# RF_Ticketing_Slave.net
KiCad netlist of a schematic drawn in Altium Designer
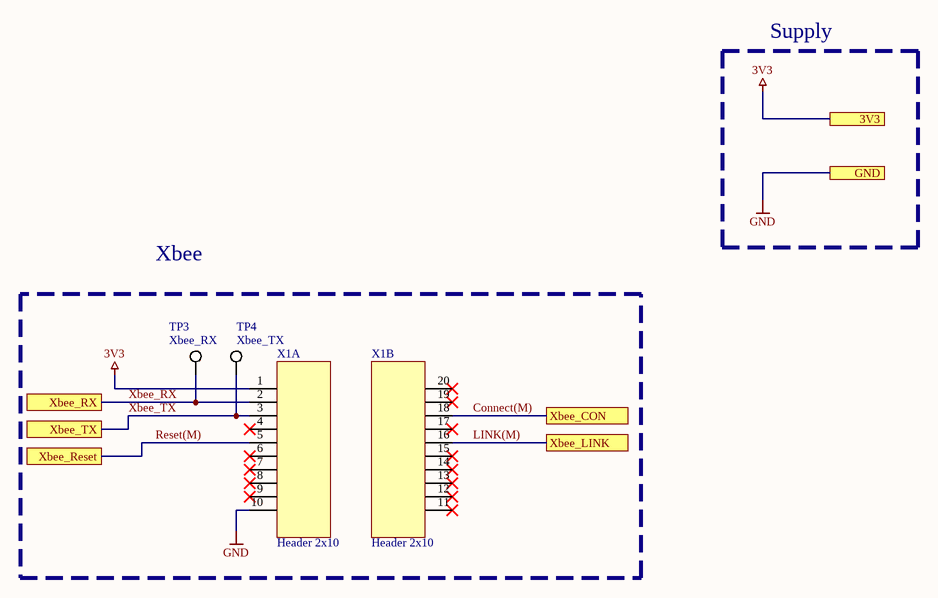
[diagram p0: RF_Ticketing_Slave.SchDoc]

(export (version "E")
  (design (tool "Eeschema 10.0.6"))
  (components
    (comp (ref "TP3")
      (value "Xbee_RX")
      (footprint "KSTN-5019_V")
      (description "Test Point, 1 Position SMD, RoHS, Tape and Reel")
      (libsource (lib "Altium Content Vault") (part "TESTPOINT_WHITE"))
    )
    (comp (ref "TP4")
      (value "Xbee_TX")
      (footprint "KSTN-5019_V")
      (description "Test Point, 1 Position SMD, RoHS, Tape and Reel")
      (libsource (lib "Altium Content Vault") (part "TESTPOINT_WHITE"))
    )
    (comp (ref "X1")
      (value "Header 2x10")
      (footprint "ZB-SB")
      (description "Header 2x10\r\nXbee de letml(1623) ou xbee XB24CAUIT-001")
      (libsource (lib "PCB_Ticketing_Slave") (part "HDR ZB-SB 2x10_1"))
    )
  )
  (nets
    (net (code "1") (name "/Connect(M)") (class "Default") (node (ref "X1") (pin "18") (pintype "passive")))
    (net (code "2") (name "/LINK(M)") (class "Default") (node (ref "X1") (pin "16") (pintype "passive")))
    (net (code "3") (name "/Reset(M)") (class "Default") (node (ref "X1") (pin "5") (pintype "passive")))
    (net (code "4") (name "/Xbee_RX") (class "Default")
      (node (ref "TP3") (pin "1") (pinfunction "1_1") (pintype "passive"))
      (node (ref "X1") (pin "2") (pintype "passive"))
    )
    (net (code "5") (name "/Xbee_TX") (class "Default")
      (node (ref "TP4") (pin "1") (pinfunction "1_1") (pintype "passive"))
      (node (ref "X1") (pin "3") (pintype "passive"))
    )
    (net (code "6") (name "3V3") (class "Default") (node (ref "X1") (pin "1") (pintype "passive")))
    (net (code "7") (name "GND") (class "Default") (node (ref "X1") (pin "10") (pintype "passive")))
    (net (code "8") (name "unconnected-(X1-Pad4)") (class "Default")
      (node (ref "X1") (pin "4") (pintype "passive+no_connect"))
    )
    (net (code "9") (name "unconnected-(X1-Pad6)") (class "Default")
      (node (ref "X1") (pin "6") (pintype "passive+no_connect"))
    )
    (net (code "10") (name "unconnected-(X1-Pad7)") (class "Default")
      (node (ref "X1") (pin "7") (pintype "passive+no_connect"))
    )
    (net (code "11") (name "unconnected-(X1-Pad8)") (class "Default")
      (node (ref "X1") (pin "8") (pintype "passive+no_connect"))
    )
    (net (code "12") (name "unconnected-(X1-Pad9)") (class "Default")
      (node (ref "X1") (pin "9") (pintype "passive+no_connect"))
    )
    (net (code "13") (name "unconnected-(X1-Pad11)") (class "Default")
      (node (ref "X1") (pin "11") (pintype "passive+no_connect"))
    )
    (net (code "14") (name "unconnected-(X1-Pad12)") (class "Default")
      (node (ref "X1") (pin "12") (pintype "passive+no_connect"))
    )
    (net (code "15") (name "unconnected-(X1-Pad13)") (class "Default")
      (node (ref "X1") (pin "13") (pintype "passive+no_connect"))
    )
    (net (code "16") (name "unconnected-(X1-Pad14)") (class "Default")
      (node (ref "X1") (pin "14") (pintype "passive+no_connect"))
    )
    (net (code "17") (name "unconnected-(X1-Pad15)") (class "Default")
      (node (ref "X1") (pin "15") (pintype "passive+no_connect"))
    )
    (net (code "18") (name "unconnected-(X1-Pad17)") (class "Default")
      (node (ref "X1") (pin "17") (pintype "passive+no_connect"))
    )
    (net (code "19") (name "unconnected-(X1-Pad19)") (class "Default")
      (node (ref "X1") (pin "19") (pintype "passive+no_connect"))
    )
    (net (code "20") (name "unconnected-(X1-Pad20)") (class "Default")
      (node (ref "X1") (pin "20") (pintype "passive+no_connect"))
    )
  )
)
